# motorboard.net
KiCad netlist of a schematic drawn in EAGLE
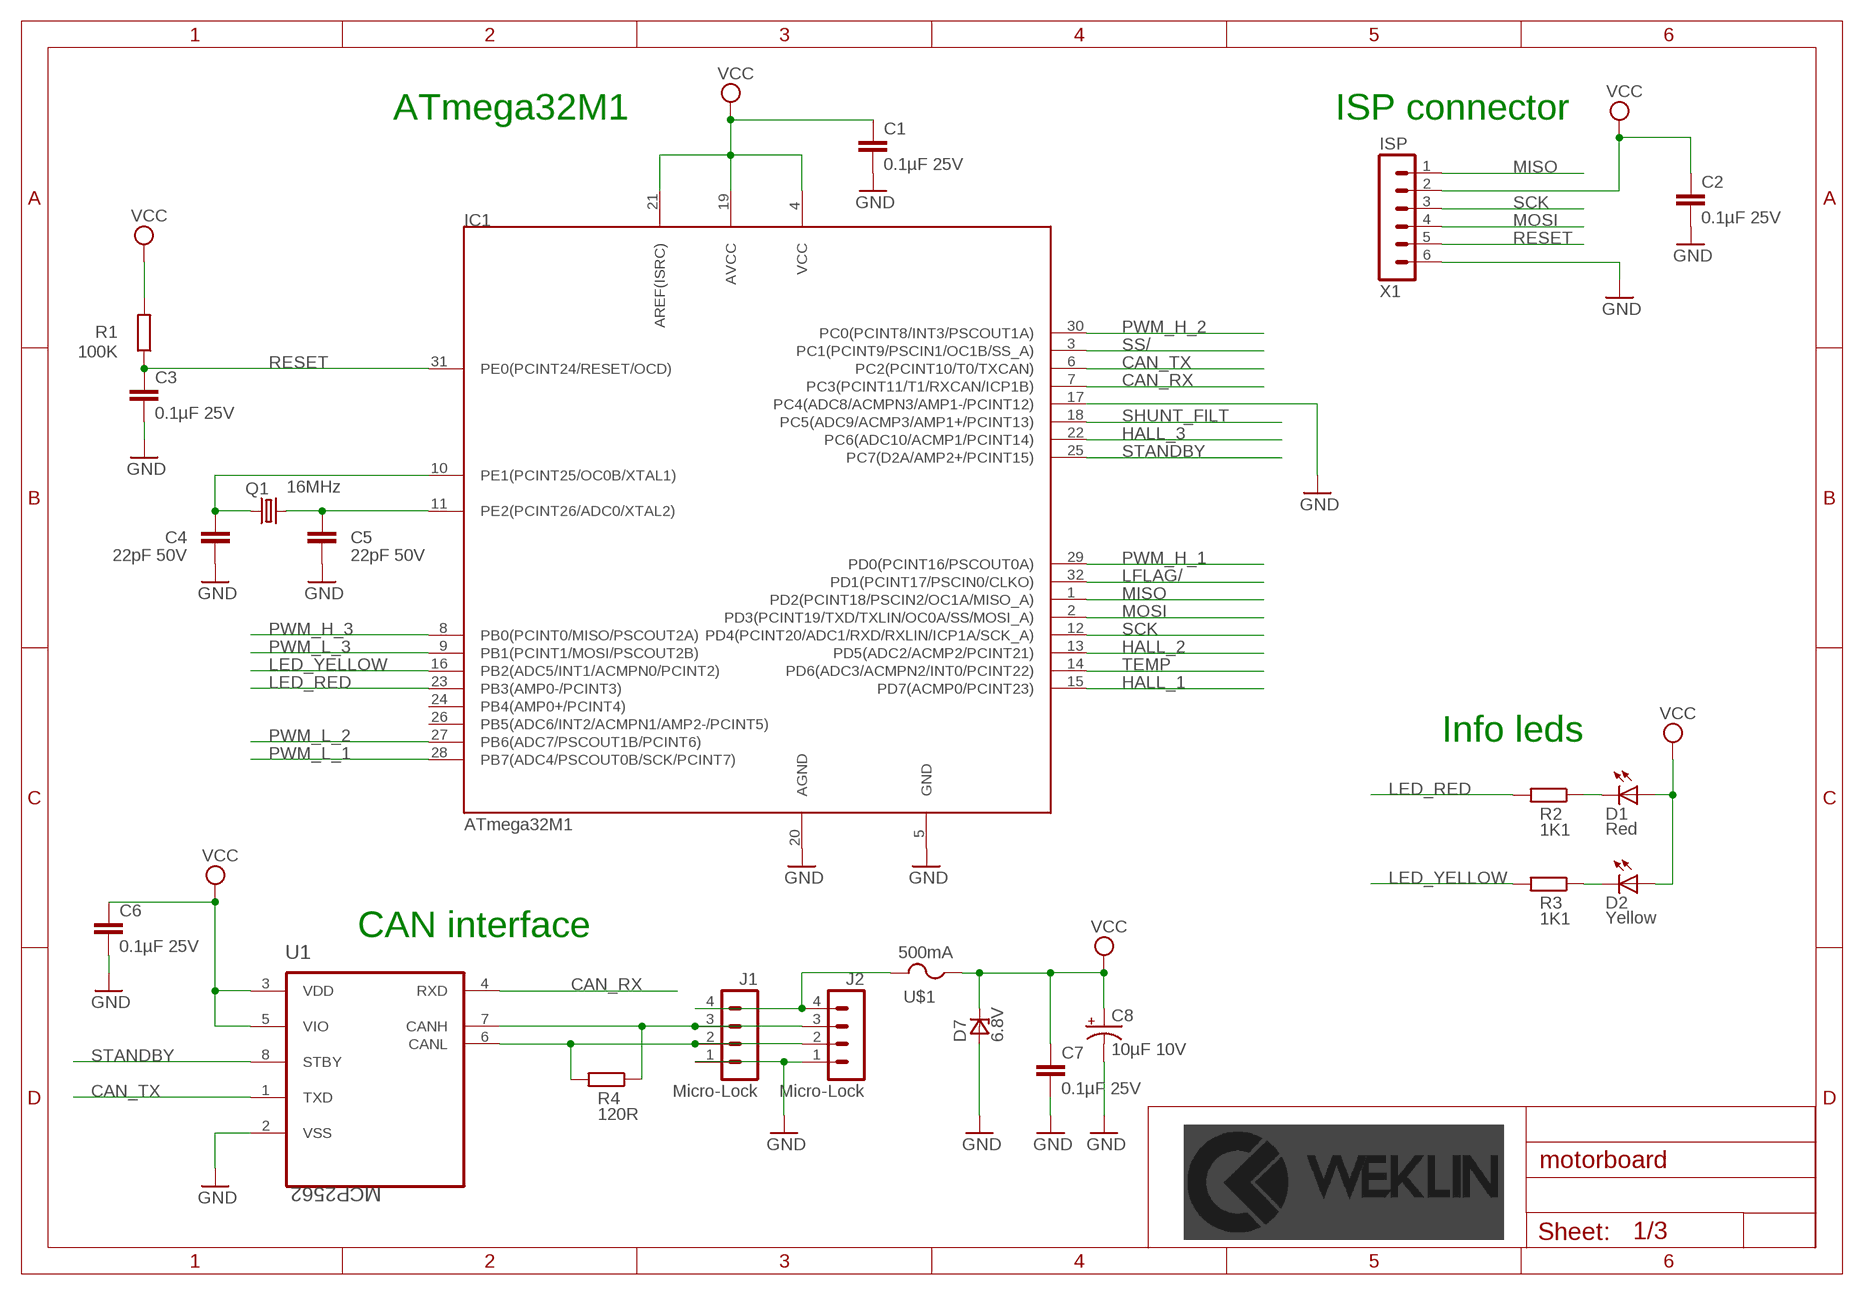
[diagram p0: schematic, sheet 1]
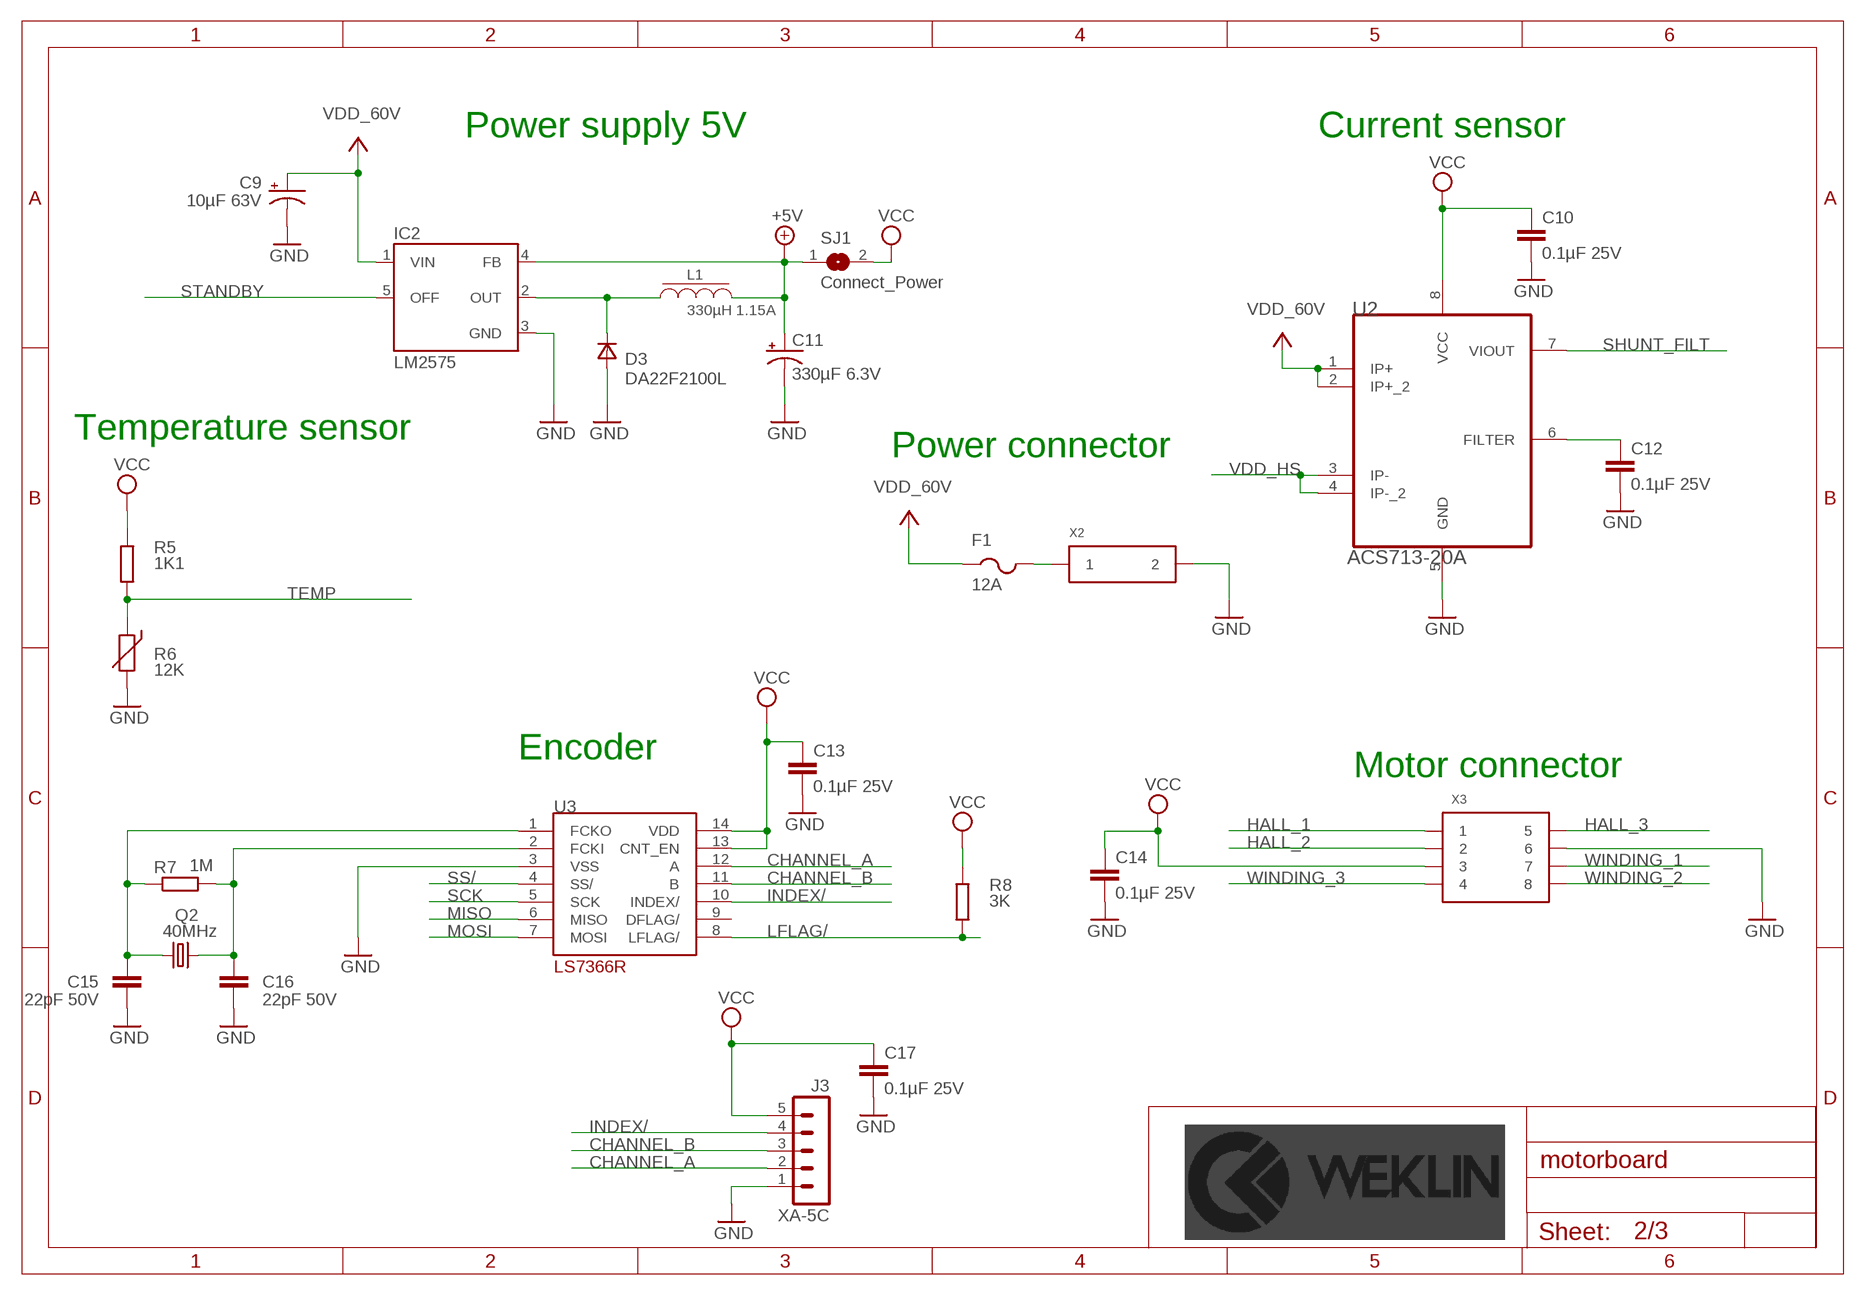
[diagram p1: schematic, sheet 2]
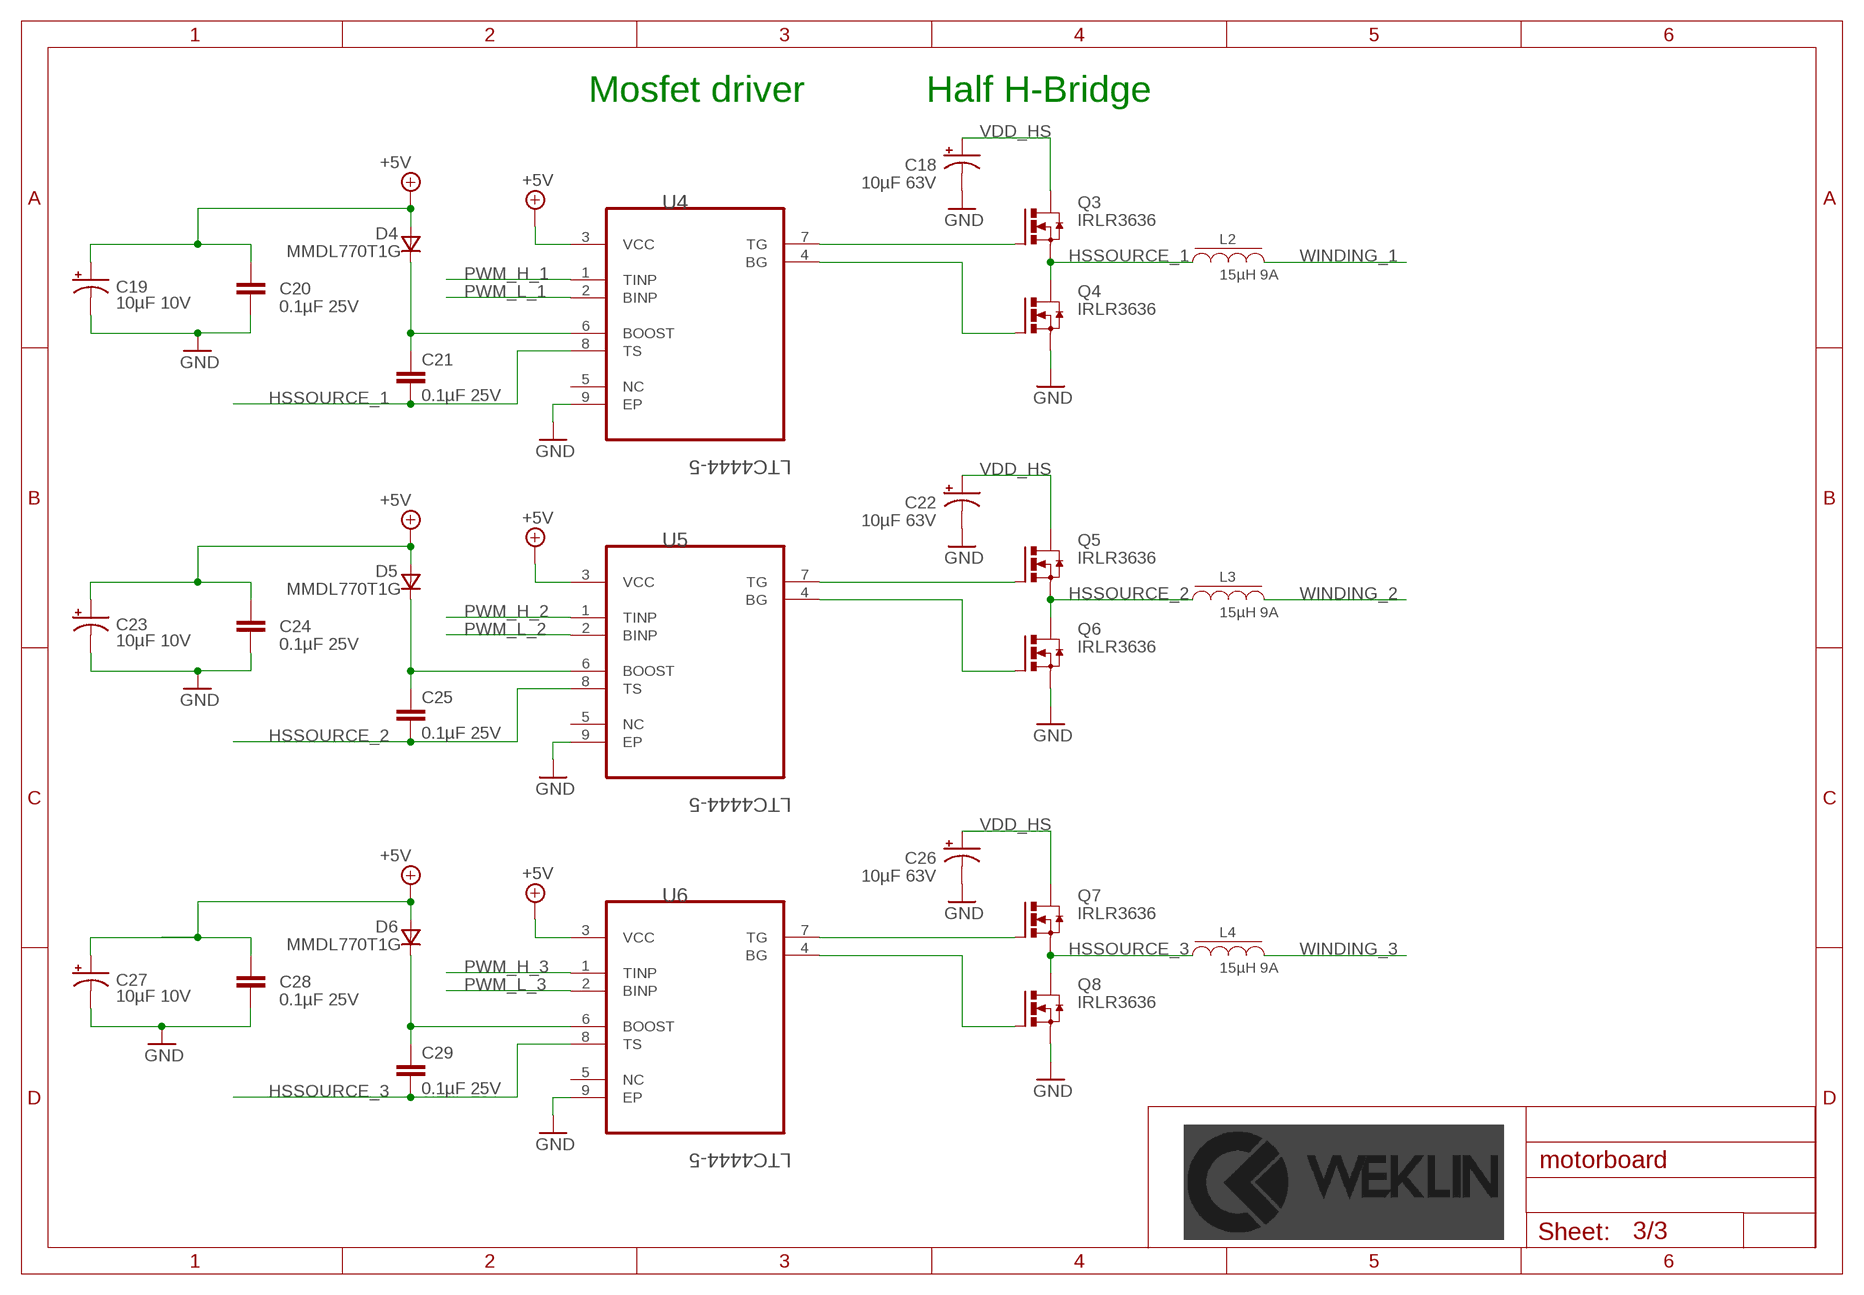
[diagram p2: schematic, sheet 3]

(export (version "E")
  (design (tool "Eeschema 10.0.6"))
  (components
    (comp (ref "C18")
      (value "10µF 63V")
      (footprint "eagle-import:153CLV-1010")
      (fields (field (name "MANUFACTURER") "Nichicon") (field (name "MPN") "UUX1J101MNL1GS"))
      (libsource (lib "eagle-import") (part "CAPACITOR_POL-100µF-63V(+-10%)(1010)"))
    )
    (comp (ref "C19")
      (value "10µF 10V")
      (footprint "eagle-import:EIA3216")
      (fields (field (name "MANUFACTURER") "Kemet") (field (name "MPN") "T491A106K010AT"))
      (libsource (lib "eagle-import") (part "CAPACITOR_POL-10µF-10V(+-10%)(3216)"))
    )
    (comp (ref "C20")
      (value "0.1µF 25V")
      (footprint "eagle-import:C2012")
      (fields (field (name "MANUFACTURER") "AVX") (field (name "MPN") "08053C104KAT2A"))
      (libsource (lib "eagle-import") (part "CAPACITOR_NON_POL-0.1µF-25V(+-10%)(2012)"))
    )
    (comp (ref "C21")
      (value "0.1µF 25V")
      (footprint "eagle-import:C2012")
      (fields (field (name "MANUFACTURER") "AVX") (field (name "MPN") "08053C104KAT2A"))
      (libsource (lib "eagle-import") (part "CAPACITOR_NON_POL-0.1µF-25V(+-10%)(2012)"))
    )
    (comp (ref "C22")
      (value "10µF 63V")
      (footprint "eagle-import:153CLV-1010")
      (fields (field (name "MANUFACTURER") "Nichicon") (field (name "MPN") "UUX1J101MNL1GS"))
      (libsource (lib "eagle-import") (part "CAPACITOR_POL-100µF-63V(+-10%)(1010)"))
    )
    (comp (ref "C23")
      (value "10µF 10V")
      (footprint "eagle-import:EIA3216")
      (fields (field (name "MANUFACTURER") "Kemet") (field (name "MPN") "T491A106K010AT"))
      (libsource (lib "eagle-import") (part "CAPACITOR_POL-10µF-10V(+-10%)(3216)"))
    )
    (comp (ref "C24")
      (value "0.1µF 25V")
      (footprint "eagle-import:C2012")
      (fields (field (name "MANUFACTURER") "AVX") (field (name "MPN") "08053C104KAT2A"))
      (libsource (lib "eagle-import") (part "CAPACITOR_NON_POL-0.1µF-25V(+-10%)(2012)"))
    )
    (comp (ref "C25")
      (value "0.1µF 25V")
      (footprint "eagle-import:C2012")
      (fields (field (name "MANUFACTURER") "AVX") (field (name "MPN") "08053C104KAT2A"))
      (libsource (lib "eagle-import") (part "CAPACITOR_NON_POL-0.1µF-25V(+-10%)(2012)"))
    )
    (comp (ref "C26")
      (value "10µF 63V")
      (footprint "eagle-import:153CLV-1010")
      (fields (field (name "MANUFACTURER") "Nichicon") (field (name "MPN") "UUX1J101MNL1GS"))
      (libsource (lib "eagle-import") (part "CAPACITOR_POL-100µF-63V(+-10%)(1010)"))
    )
    (comp (ref "C27")
      (value "10µF 10V")
      (footprint "eagle-import:EIA3216")
      (fields (field (name "MANUFACTURER") "Kemet") (field (name "MPN") "T491A106K010AT"))
      (libsource (lib "eagle-import") (part "CAPACITOR_POL-10µF-10V(+-10%)(3216)"))
    )
    (comp (ref "C28")
      (value "0.1µF 25V")
      (footprint "eagle-import:C2012")
      (fields (field (name "MANUFACTURER") "AVX") (field (name "MPN") "08053C104KAT2A"))
      (libsource (lib "eagle-import") (part "CAPACITOR_NON_POL-0.1µF-25V(+-10%)(2012)"))
    )
    (comp (ref "C29")
      (value "0.1µF 25V")
      (footprint "eagle-import:C2012")
      (fields (field (name "MANUFACTURER") "AVX") (field (name "MPN") "08053C104KAT2A"))
      (libsource (lib "eagle-import") (part "CAPACITOR_NON_POL-0.1µF-25V(+-10%)(2012)"))
    )
    (comp (ref "D4")
      (value "MMDL770T1G")
      (footprint "eagle-import:SOD323")
      (libsource (lib "eagle-import") (part "DIODE-MMDL770T1G"))
    )
    (comp (ref "D5")
      (value "MMDL770T1G")
      (footprint "eagle-import:SOD323")
      (libsource (lib "eagle-import") (part "DIODE-MMDL770T1G"))
    )
    (comp (ref "D6")
      (value "MMDL770T1G")
      (footprint "eagle-import:SOD323")
      (libsource (lib "eagle-import") (part "DIODE-MMDL770T1G"))
    )
    (comp (ref "L2")
      (value "15µH 9A")
      (footprint "eagle-import:DRA127")
      (fields (field (name "MPN") "SRP1265A-150M"))
      (libsource (lib "eagle-import") (part "SRP1265A-150M"))
    )
    (comp (ref "L3")
      (value "15µH 9A")
      (footprint "eagle-import:DRA127")
      (fields (field (name "MPN") "SRP1265A-150M"))
      (libsource (lib "eagle-import") (part "SRP1265A-150M"))
    )
    (comp (ref "L4")
      (value "15µH 9A")
      (footprint "eagle-import:DRA127")
      (fields (field (name "MPN") "SRP1265A-150M"))
      (libsource (lib "eagle-import") (part "SRP1265A-150M"))
    )
    (comp (ref "Q3")
      (value "IRLR3636")
      (footprint "eagle-import:TO252")
      (fields (field (name "MANUFACTURER") "International Rectifier") (field (name "MPN") "IRLR3636PbF"))
      (libsource (lib "eagle-import") (part "IRLR3636"))
    )
    (comp (ref "Q4")
      (value "IRLR3636")
      (footprint "eagle-import:TO252")
      (fields (field (name "MANUFACTURER") "International Rectifier") (field (name "MPN") "IRLR3636PbF"))
      (libsource (lib "eagle-import") (part "IRLR3636"))
    )
    (comp (ref "Q5")
      (value "IRLR3636")
      (footprint "eagle-import:TO252")
      (fields (field (name "MANUFACTURER") "International Rectifier") (field (name "MPN") "IRLR3636PbF"))
      (libsource (lib "eagle-import") (part "IRLR3636"))
    )
    (comp (ref "Q6")
      (value "IRLR3636")
      (footprint "eagle-import:TO252")
      (fields (field (name "MANUFACTURER") "International Rectifier") (field (name "MPN") "IRLR3636PbF"))
      (libsource (lib "eagle-import") (part "IRLR3636"))
    )
    (comp (ref "Q7")
      (value "IRLR3636")
      (footprint "eagle-import:TO252")
      (fields (field (name "MANUFACTURER") "International Rectifier") (field (name "MPN") "IRLR3636PbF"))
      (libsource (lib "eagle-import") (part "IRLR3636"))
    )
    (comp (ref "Q8")
      (value "IRLR3636")
      (footprint "eagle-import:TO252")
      (fields (field (name "MANUFACTURER") "International Rectifier") (field (name "MPN") "IRLR3636PbF"))
      (libsource (lib "eagle-import") (part "IRLR3636"))
    )
    (comp (ref "U4")
      (value "LTC4444-5")
      (footprint "eagle-import:MSOP8")
      (fields (field (name "MPN") "LTC4444EMS8E-5#PBF"))
      (libsource (lib "eagle-import") (part "LTC4444EMS8EPBF"))
    )
    (comp (ref "U5")
      (value "LTC4444-5")
      (footprint "eagle-import:MSOP8")
      (fields (field (name "MPN") "LTC4444EMS8E-5#PBF"))
      (libsource (lib "eagle-import") (part "LTC4444EMS8EPBF"))
    )
    (comp (ref "U6")
      (value "LTC4444-5")
      (footprint "eagle-import:MSOP8")
      (fields (field (name "MPN") "LTC4444EMS8E-5#PBF"))
      (libsource (lib "eagle-import") (part "LTC4444EMS8EPBF"))
    )
    (comp (ref "C9")
      (value "10µF 63V")
      (footprint "eagle-import:153CLV-1010")
      (fields (field (name "MANUFACTURER") "Nichicon") (field (name "MPN") "UUX1J101MNL1GS"))
      (libsource (lib "eagle-import") (part "CAPACITOR_POL-100µF-63V(+-10%)(1010)"))
    )
    (comp (ref "C10")
      (value "0.1µF 25V")
      (footprint "eagle-import:C2012")
      (fields (field (name "MANUFACTURER") "AVX") (field (name "MPN") "08053C104KAT2A"))
      (libsource (lib "eagle-import") (part "CAPACITOR_NON_POL-0.1µF-25V(+-10%)(2012)"))
    )
    (comp (ref "C11")
      (value "330µF 6.3V")
      (footprint "eagle-import:EIA7343")
      (fields (field (name "MANUFACTURER") "Kemet") (field (name "MPN") "T491D337K006AT"))
      (libsource (lib "eagle-import") (part "CAPACITOR_POL-330µF-6.3V(+-10%)(7343)"))
    )
    (comp (ref "C12")
      (value "0.1µF 25V")
      (footprint "eagle-import:C2012")
      (fields (field (name "MANUFACTURER") "AVX") (field (name "MPN") "08053C104KAT2A"))
      (libsource (lib "eagle-import") (part "CAPACITOR_NON_POL-0.1µF-25V(+-10%)(2012)"))
    )
    (comp (ref "C13")
      (value "0.1µF 25V")
      (footprint "eagle-import:C2012")
      (fields (field (name "MANUFACTURER") "AVX") (field (name "MPN") "08053C104KAT2A"))
      (libsource (lib "eagle-import") (part "CAPACITOR_NON_POL-0.1µF-25V(+-10%)(2012)"))
    )
    (comp (ref "C14")
      (value "0.1µF 25V")
      (footprint "eagle-import:C2012")
      (fields (field (name "MANUFACTURER") "AVX") (field (name "MPN") "08053C104KAT2A"))
      (libsource (lib "eagle-import") (part "CAPACITOR_NON_POL-0.1µF-25V(+-10%)(2012)"))
    )
    (comp (ref "C15")
      (value "22pF 50V")
      (footprint "eagle-import:C2012")
      (fields (field (name "MANUFACTURER") "Multicomp") (field (name "MPN") "MC0805N220J500CT"))
      (libsource (lib "eagle-import") (part "CAPACITOR_NON_POL-22PF-50V(+-5%)(2012)"))
    )
    (comp (ref "C16")
      (value "22pF 50V")
      (footprint "eagle-import:C2012")
      (fields (field (name "MANUFACTURER") "Multicomp") (field (name "MPN") "MC0805N220J500CT"))
      (libsource (lib "eagle-import") (part "CAPACITOR_NON_POL-22PF-50V(+-5%)(2012)"))
    )
    (comp (ref "C17")
      (value "0.1µF 25V")
      (footprint "eagle-import:C2012")
      (fields (field (name "MANUFACTURER") "AVX") (field (name "MPN") "08053C104KAT2A"))
      (libsource (lib "eagle-import") (part "CAPACITOR_NON_POL-0.1µF-25V(+-10%)(2012)"))
    )
    (comp (ref "D3")
      (value "DA22F2100L")
      (footprint "eagle-import:SOD323")
      (libsource (lib "eagle-import") (part "DIODE-DA22F2100L"))
    )
    (comp (ref "F1")
      (value "12A")
      (footprint "eagle-import:R3216")
      (fields (field (name "MPN") "3413.0329.22"))
      (libsource (lib "eagle-import") (part "PTCFUSE-3216(1206)"))
    )
    (comp (ref "IC2")
      (value "LM2575")
      (footprint "eagle-import:TO263-5")
      (fields (field (name "MPN") "LM2575HVS-5.0/NOPB"))
      (libsource (lib "eagle-import") (part "LM2575-TO263"))
    )
    (comp (ref "J3")
      (value "XA-5C")
      (footprint "eagle-import:S05B-XASK-1")
      (fields (field (name "MPN") "S05B-XASK-1(LF)(SN)"))
      (libsource (lib "eagle-import") (part "XA-5-RIGHT_ANGLE"))
    )
    (comp (ref "L1")
      (value "330µH 1.15A")
      (footprint "eagle-import:DRA124")
      (fields (field (name "MPN") "SRR1260A-331K"))
      (libsource (lib "eagle-import") (part "SRR1260A-331K"))
    )
    (comp (ref "Q2")
      (value "40MHz")
      (footprint "eagle-import:SMD_KX7")
      (fields (field (name "MANUFACTURER") "Epson") (field (name "MPN") "X1E0000210488 TSX-3225 "))
      (libsource (lib "eagle-import") (part "CRYSTAL-40MHZ_SMD(3225)"))
    )
    (comp (ref "R5")
      (value "1K1")
      (footprint "eagle-import:R2012")
      (fields (field (name "MANUFACTURER") "Multicomp") (field (name "MPN") "MC0805S8F1101T5E"))
      (libsource (lib "eagle-import") (part "RESISTOR-1K1(+-1%)(2012)"))
    )
    (comp (ref "R6")
      (value "12K")
      (footprint "eagle-import:T2012")
      (fields (field (name "MPN") "NB12L00123KBB"))
      (libsource (lib "eagle-import") (part "NB12L00123KBB-2012(0805)"))
    )
    (comp (ref "R7")
      (value "1M")
      (footprint "eagle-import:R2012")
      (fields (field (name "MPN") "MCWR08X1004FTL"))
      (libsource (lib "eagle-import") (part "RESISTOR-1M(+-1%)(2012)"))
    )
    (comp (ref "R8")
      (value "3K")
      (footprint "eagle-import:R2012")
      (fields (field (name "MPN") "MC0805S8F3001T5E"))
      (libsource (lib "eagle-import") (part "RESISTOR-3K(+-1%)(2012)"))
    )
    (comp (ref "SJ1")
      (value "Connect_Power")
      (footprint "eagle-import:SJ")
      (fields (field (name "MPN") "N.A."))
      (libsource (lib "eagle-import") (part "JUMPER_PCB"))
    )
    (comp (ref "U2")
      (value "ACS713-20A")
      (footprint "eagle-import:SOIC8")
      (fields (field (name "MPN") "ACS713ELCTR-20A-T"))
      (libsource (lib "eagle-import") (part "ASC713713ELCTR-20A-T"))
    )
    (comp (ref "U3")
      (value "LS7366R")
      (footprint "eagle-import:TSSOP14")
      (fields (field (name "MPN") "LS7366R-TS"))
      (libsource (lib "eagle-import") (part "LS7366R-TS-TSSOP14"))
    )
    (comp (ref "X2")
      (value "Mini-Fit")
      (footprint "eagle-import:5569-02")
      (fields (field (name "MANUFACTURER") "Molex") (field (name "MPN") "39-29-1028"))
      (libsource (lib "eagle-import") (part "MINI-FIT-JR-025569-NA1"))
    )
    (comp (ref "X3")
      (value "Mini-Fit")
      (footprint "eagle-import:5569-08")
      (fields (field (name "MANUFACTURER") "MOLEX") (field (name "MPN") "39-29-1088"))
      (libsource (lib "eagle-import") (part "MINI-FIT-JR-085569-NA1"))
    )
    (comp (ref "C1")
      (value "0.1µF 25V")
      (footprint "eagle-import:C2012")
      (fields (field (name "MANUFACTURER") "AVX") (field (name "MPN") "08053C104KAT2A"))
      (libsource (lib "eagle-import") (part "CAPACITOR_NON_POL-0.1µF-25V(+-10%)(2012)"))
    )
    (comp (ref "C2")
      (value "0.1µF 25V")
      (footprint "eagle-import:C2012")
      (fields (field (name "MANUFACTURER") "AVX") (field (name "MPN") "08053C104KAT2A"))
      (libsource (lib "eagle-import") (part "CAPACITOR_NON_POL-0.1µF-25V(+-10%)(2012)"))
    )
    (comp (ref "C3")
      (value "0.1µF 25V")
      (footprint "eagle-import:C2012")
      (fields (field (name "MANUFACTURER") "AVX") (field (name "MPN") "08053C104KAT2A"))
      (libsource (lib "eagle-import") (part "CAPACITOR_NON_POL-0.1µF-25V(+-10%)(2012)"))
    )
    (comp (ref "C4")
      (value "22pF 50V")
      (footprint "eagle-import:C2012")
      (fields (field (name "MANUFACTURER") "Multicomp") (field (name "MPN") "MC0805N220J500CT"))
      (libsource (lib "eagle-import") (part "CAPACITOR_NON_POL-22PF-50V(+-5%)(2012)"))
    )
    (comp (ref "C5")
      (value "22pF 50V")
      (footprint "eagle-import:C2012")
      (fields (field (name "MANUFACTURER") "Multicomp") (field (name "MPN") "MC0805N220J500CT"))
      (libsource (lib "eagle-import") (part "CAPACITOR_NON_POL-22PF-50V(+-5%)(2012)"))
    )
    (comp (ref "C6")
      (value "0.1µF 25V")
      (footprint "eagle-import:C2012")
      (fields (field (name "MANUFACTURER") "AVX") (field (name "MPN") "08053C104KAT2A"))
      (libsource (lib "eagle-import") (part "CAPACITOR_NON_POL-0.1µF-25V(+-10%)(2012)"))
    )
    (comp (ref "C7")
      (value "0.1µF 25V")
      (footprint "eagle-import:C2012")
      (fields (field (name "MANUFACTURER") "AVX") (field (name "MPN") "08053C104KAT2A"))
      (libsource (lib "eagle-import") (part "CAPACITOR_NON_POL-0.1µF-25V(+-10%)(2012)"))
    )
    (comp (ref "C8")
      (value "10µF 10V")
      (footprint "eagle-import:EIA3216")
      (fields (field (name "MANUFACTURER") "Kemet") (field (name "MPN") "T491A106K010AT"))
      (libsource (lib "eagle-import") (part "CAPACITOR_POL-10µF-10V(+-10%)(3216)"))
    )
    (comp (ref "D1")
      (value "Red")
      (footprint "eagle-import:VLD")
      (fields (field (name "MANUFACTURER") "Vishay") (field (name "MPN") "VLDS1235G"))
      (libsource (lib "eagle-import") (part "LEDVLDS1235G"))
    )
    (comp (ref "D2")
      (value "Yellow")
      (footprint "eagle-import:VLD")
      (fields (field (name "MANUFACTURER") "Vishay") (field (name "MPN") "VLDY1235G"))
      (libsource (lib "eagle-import") (part "LED-VLDY1235G"))
    )
    (comp (ref "D7")
      (value "6.8V")
      (footprint "eagle-import:DO-214AA")
      (fields (field (name "MANUFACTURER") "ON Semiconductor") (field (name "MPN") "P6SMB6.8AT3G"))
      (libsource (lib "eagle-import") (part "ZENER_UNIDIR6.8"))
    )
    (comp (ref "IC1")
      (value "ATmega32M1")
      (footprint "eagle-import:TQFP32")
      (fields (field (name "MANUFACTURER") "Atmel") (field (name "MPN") "ATmega32M1-AU"))
      (libsource (lib "eagle-import") (part "ATMEGA32M1-TQFP32"))
    )
    (comp (ref "J1")
      (value "Micro-Lock")
      (footprint "eagle-import:504195-0470")
      (fields (field (name "MANUFACTURER") "Molex") (field (name "MPN") "504195-0470"))
      (libsource (lib "eagle-import") (part "MICROLOCK-4CMS"))
    )
    (comp (ref "J2")
      (value "Micro-Lock")
      (footprint "eagle-import:504195-0470")
      (fields (field (name "MANUFACTURER") "Molex") (field (name "MPN") "504195-0470"))
      (libsource (lib "eagle-import") (part "MICROLOCK-4CMS"))
    )
    (comp (ref "Q1")
      (value "16MHz")
      (footprint "eagle-import:SMD_KX7")
      (fields (field (name "MANUFACTURER") "AEL CRYSTALS") (field (name "MPN") "E3SB16.0000F09G11AE"))
      (libsource (lib "eagle-import") (part "CRYSTAL-16MHZ_SMD(3225)"))
    )
    (comp (ref "R1")
      (value "100K")
      (footprint "eagle-import:R2012")
      (fields (field (name "MANUFACTURER") "Multicomp") (field (name "MPN") "MCWR08X1003FTL"))
      (libsource (lib "eagle-import") (part "RESISTOR-100K(+-1%)(2012)"))
    )
    (comp (ref "R2")
      (value "1K1")
      (footprint "eagle-import:R2012")
      (fields (field (name "MANUFACTURER") "Multicomp") (field (name "MPN") "MC0805S8F1101T5E"))
      (libsource (lib "eagle-import") (part "RESISTOR-1K1(+-1%)(2012)"))
    )
    (comp (ref "R3")
      (value "1K1")
      (footprint "eagle-import:R2012")
      (fields (field (name "MANUFACTURER") "Multicomp") (field (name "MPN") "MC0805S8F1101T5E"))
      (libsource (lib "eagle-import") (part "RESISTOR-1K1(+-1%)(2012)"))
    )
    (comp (ref "R4")
      (value "120R")
      (footprint "eagle-import:R2012")
      (fields (field (name "MANUFACTURER") "Multicomp") (field (name "MPN") "MCWR08X1200FTL"))
      (libsource (lib "eagle-import") (part "RESISTOR-120R(+-1%)(2012)"))
    )
    (comp (ref "U$1")
      (value "500mA")
      (footprint "eagle-import:EIARS-481-2")
      (fields (field (name "MANUFACTURER") "Littlefuse") (field (name "MPN") "0451.500MRL"))
      (libsource (lib "eagle-import") (part "FUSE"))
    )
    (comp (ref "U1")
      (value "MCP2562")
      (footprint "eagle-import:SOIC8")
      (fields (field (name "MANUFACTURER") "Microchip") (field (name "MPN") "MCP2562-E/SN"))
      (libsource (lib "eagle-import") (part "MCP2562-E/SN-SOIC8"))
    )
    (comp (ref "X1")
      (value "ISP")
      (footprint "eagle-import:MINITEK_127_6WAY_SMD")
      (fields (field (name "MANUFACTURER") "Minitek") (field (name "MPN") "20021121-00006C4LF"))
      (libsource (lib "eagle-import") (part "MINITEK_127_6WAYS-SMD"))
    )
  )
  (nets
    (net (code "1") (name "+5V") (class "Default")
      (node (ref "C11") (pin "A") (pinfunction "+_A") (pintype "passive"))
      (node (ref "C19") (pin "A") (pinfunction "+_A") (pintype "passive"))
      (node (ref "C20") (pin "1") (pinfunction "1_1") (pintype "passive"))
      (node (ref "C23") (pin "A") (pinfunction "+_A") (pintype "passive"))
      (node (ref "C24") (pin "1") (pinfunction "1_1") (pintype "passive"))
      (node (ref "C27") (pin "A") (pinfunction "+_A") (pintype "passive"))
      (node (ref "C28") (pin "1") (pinfunction "1_1") (pintype "passive"))
      (node (ref "D4") (pin "2") (pinfunction "A_2") (pintype "passive"))
      (node (ref "D5") (pin "2") (pinfunction "A_2") (pintype "passive"))
      (node (ref "D6") (pin "2") (pinfunction "A_2") (pintype "passive"))
      (node (ref "IC2") (pin "4") (pinfunction "FB_4") (pintype "input"))
      (node (ref "L1") (pin "2") (pinfunction "2_2") (pintype "passive"))
      (node (ref "SJ1") (pin "1") (pinfunction "1_1") (pintype "passive"))
      (node (ref "U4") (pin "3") (pinfunction "VCC_3") (pintype "power_in"))
      (node (ref "U5") (pin "3") (pinfunction "VCC_3") (pintype "power_in"))
      (node (ref "U6") (pin "3") (pinfunction "VCC_3") (pintype "power_in"))
    )
    (net (code "2") (name "CAN_RX") (class "Default")
      (node (ref "IC1") (pin "7") (pinfunction "PC3(PCINT11/T1/RXCAN/ICP1B)_7") (pintype "bidirectional"))
      (node (ref "U1") (pin "4") (pinfunction "RXD_4") (pintype "output"))
    )
    (net (code "3") (name "CAN_TX") (class "Default")
      (node (ref "IC1") (pin "6") (pinfunction "PC2(PCINT10/T0/TXCAN)_6") (pintype "bidirectional"))
      (node (ref "U1") (pin "1") (pinfunction "TXD_1") (pintype "input"))
    )
    (net (code "4") (name "CHANNEL_A") (class "Default")
      (node (ref "J3") (pin "2") (pinfunction "2_2") (pintype "passive"))
      (node (ref "U3") (pin "12") (pinfunction "A_12") (pintype "bidirectional"))
    )
    (net (code "5") (name "CHANNEL_B") (class "Default")
      (node (ref "J3") (pin "3") (pinfunction "3_3") (pintype "passive"))
      (node (ref "U3") (pin "11") (pinfunction "B_11") (pintype "bidirectional"))
    )
    (net (code "6") (name "GND") (class "Default")
      (node (ref "C1") (pin "2") (pinfunction "2_2") (pintype "passive"))
      (node (ref "C10") (pin "2") (pinfunction "2_2") (pintype "passive"))
      (node (ref "C11") (pin "C") (pinfunction "-_C") (pintype "passive"))
      (node (ref "C12") (pin "2") (pinfunction "2_2") (pintype "passive"))
      (node (ref "C13") (pin "2") (pinfunction "2_2") (pintype "passive"))
      (node (ref "C14") (pin "2") (pinfunction "2_2") (pintype "passive"))
      (node (ref "C15") (pin "2") (pinfunction "2_2") (pintype "passive"))
      (node (ref "C16") (pin "2") (pinfunction "2_2") (pintype "passive"))
      (node (ref "C17") (pin "2") (pinfunction "2_2") (pintype "passive"))
      (node (ref "C18") (pin "-") (pinfunction "-_-") (pintype "passive"))
      (node (ref "C19") (pin "C") (pinfunction "-_C") (pintype "passive"))
      (node (ref "C2") (pin "2") (pinfunction "2_2") (pintype "passive"))
      (node (ref "C20") (pin "2") (pinfunction "2_2") (pintype "passive"))
      (node (ref "C22") (pin "-") (pinfunction "-_-") (pintype "passive"))
      (node (ref "C23") (pin "C") (pinfunction "-_C") (pintype "passive"))
      (node (ref "C24") (pin "2") (pinfunction "2_2") (pintype "passive"))
      (node (ref "C26") (pin "-") (pinfunction "-_-") (pintype "passive"))
      (node (ref "C27") (pin "C") (pinfunction "-_C") (pintype "passive"))
      (node (ref "C28") (pin "2") (pinfunction "2_2") (pintype "passive"))
      (node (ref "C3") (pin "2") (pinfunction "2_2") (pintype "passive"))
      (node (ref "C4") (pin "2") (pinfunction "2_2") (pintype "passive"))
      (node (ref "C5") (pin "2") (pinfunction "2_2") (pintype "passive"))
      (node (ref "C6") (pin "2") (pinfunction "2_2") (pintype "passive"))
      (node (ref "C7") (pin "2") (pinfunction "2_2") (pintype "passive"))
      (node (ref "C8") (pin "C") (pinfunction "-_C") (pintype "passive"))
      (node (ref "C9") (pin "-") (pinfunction "-_-") (pintype "passive"))
      (node (ref "D3") (pin "2") (pinfunction "A_2") (pintype "passive"))
      (node (ref "D7") (pin "A") (pinfunction "A_A") (pintype "passive"))
      (node (ref "IC1") (pin "17") (pinfunction "PC4(ADC8/ACMPN3/AMP1-/PCINT12)_17") (pintype "bidirectional"))
      (node (ref "IC1") (pin "20") (pinfunction "AGND_20") (pintype "power_in"))
      (node (ref "IC1") (pin "5") (pinfunction "GND_5") (pintype "power_in"))
      (node (ref "IC2") (pin "3") (pinfunction "GND_3") (pintype "power_in"))
      (node (ref "J1") (pin "1") (pinfunction "1_1") (pintype "passive"))
      (node (ref "J2") (pin "1") (pinfunction "1_1") (pintype "passive"))
      (node (ref "J3") (pin "1") (pinfunction "1_1") (pintype "passive"))
      (node (ref "Q4") (pin "3") (pinfunction "S_3") (pintype "passive"))
      (node (ref "Q6") (pin "3") (pinfunction "S_3") (pintype "passive"))
      (node (ref "Q8") (pin "3") (pinfunction "S_3") (pintype "passive"))
      (node (ref "R6") (pin "2") (pinfunction "2_2") (pintype "passive"))
      (node (ref "U1") (pin "2") (pinfunction "VSS_2") (pintype "power_in"))
      (node (ref "U2") (pin "5") (pinfunction "GND_5") (pintype "passive"))
      (node (ref "U3") (pin "3") (pinfunction "VSS_3") (pintype "bidirectional"))
      (node (ref "U4") (pin "9") (pinfunction "EP_9") (pintype "passive"))
      (node (ref "U5") (pin "9") (pinfunction "EP_9") (pintype "passive"))
      (node (ref "U6") (pin "9") (pinfunction "EP_9") (pintype "passive"))
      (node (ref "X1") (pin "6") (pinfunction "6_6") (pintype "passive"))
      (node (ref "X2") (pin "P2") (pinfunction "2_P2") (pintype "bidirectional"))
      (node (ref "X3") (pin "P6") (pinfunction "6_P6") (pintype "bidirectional"))
    )
    (net (code "7") (name "HALL_1") (class "Default")
      (node (ref "IC1") (pin "15") (pinfunction "PD7(ACMP0/PCINT23)_15") (pintype "bidirectional"))
      (node (ref "X3") (pin "P1") (pinfunction "1_P1") (pintype "bidirectional"))
    )
    (net (code "8") (name "HALL_2") (class "Default")
      (node (ref "IC1") (pin "13") (pinfunction "PD5(ADC2/ACMP2/PCINT21)_13") (pintype "bidirectional"))
      (node (ref "X3") (pin "P2") (pinfunction "2_P2") (pintype "bidirectional"))
    )
    (net (code "9") (name "HALL_3") (class "Default")
      (node (ref "IC1") (pin "22") (pinfunction "PC6(ADC10/ACMP1/PCINT14)_22") (pintype "bidirectional"))
      (node (ref "X3") (pin "P5") (pinfunction "5_P5") (pintype "bidirectional"))
    )
    (net (code "10") (name "HSSOURCE_1") (class "Default")
      (node (ref "C21") (pin "2") (pinfunction "2_2") (pintype "passive"))
      (node (ref "L2") (pin "1") (pinfunction "1_1") (pintype "passive"))
      (node (ref "Q3") (pin "3") (pinfunction "S_3") (pintype "passive"))
      (node (ref "Q4") (pin "4") (pinfunction "D_4") (pintype "passive"))
      (node (ref "U4") (pin "8") (pinfunction "TS_8") (pintype "input"))
    )
    (net (code "11") (name "HSSOURCE_2") (class "Default")
      (node (ref "C25") (pin "2") (pinfunction "2_2") (pintype "passive"))
      (node (ref "L3") (pin "1") (pinfunction "1_1") (pintype "passive"))
      (node (ref "Q5") (pin "3") (pinfunction "S_3") (pintype "passive"))
      (node (ref "Q6") (pin "4") (pinfunction "D_4") (pintype "passive"))
      (node (ref "U5") (pin "8") (pinfunction "TS_8") (pintype "input"))
    )
    (net (code "12") (name "HSSOURCE_3") (class "Default")
      (node (ref "C29") (pin "2") (pinfunction "2_2") (pintype "passive"))
      (node (ref "L4") (pin "1") (pinfunction "1_1") (pintype "passive"))
      (node (ref "Q7") (pin "3") (pinfunction "S_3") (pintype "passive"))
      (node (ref "Q8") (pin "4") (pinfunction "D_4") (pintype "passive"))
      (node (ref "U6") (pin "8") (pinfunction "TS_8") (pintype "input"))
    )
    (net (code "13") (name "INDEX{slash}") (class "Default")
      (node (ref "J3") (pin "4") (pinfunction "4_4") (pintype "passive"))
      (node (ref "U3") (pin "10") (pinfunction "INDEX/_10") (pintype "bidirectional"))
    )
    (net (code "14") (name "LED_RED") (class "Default")
      (node (ref "IC1") (pin "23") (pinfunction "PB3(AMP0-/PCINT3)_23") (pintype "bidirectional"))
      (node (ref "R2") (pin "2") (pinfunction "2_2") (pintype "passive"))
    )
    (net (code "15") (name "LED_YELLOW") (class "Default")
      (node (ref "IC1") (pin "16") (pinfunction "PB2(ADC5/INT1/ACMPN0/PCINT2)_16") (pintype "bidirectional"))
      (node (ref "R3") (pin "2") (pinfunction "2_2") (pintype "passive"))
    )
    (net (code "16") (name "LFLAG{slash}") (class "Default")
      (node (ref "IC1") (pin "32") (pinfunction "PD1(PCINT17/PSCIN0/CLKO)_32") (pintype "bidirectional"))
      (node (ref "R8") (pin "2") (pinfunction "2_2") (pintype "passive"))
      (node (ref "U3") (pin "8") (pinfunction "LFLAG/_8") (pintype "bidirectional"))
    )
    (net (code "17") (name "MISO") (class "Default")
      (node (ref "IC1") (pin "1") (pinfunction "PD2(PCINT18/PSCIN2/OC1A/MISO_A)_1") (pintype "bidirectional"))
      (node (ref "U3") (pin "6") (pinfunction "MISO_6") (pintype "bidirectional"))
      (node (ref "X1") (pin "1") (pinfunction "1_1") (pintype "passive"))
    )
    (net (code "18") (name "MOSI") (class "Default")
      (node (ref "IC1") (pin "2") (pinfunction "PD3(PCINT19/TXD/TXLIN/OC0A/SS/MOSI_A)_2") (pintype "bidirectional"))
      (node (ref "U3") (pin "7") (pinfunction "MOSI_7") (pintype "bidirectional"))
      (node (ref "X1") (pin "4") (pinfunction "4_4") (pintype "passive"))
    )
    (net (code "19") (name "Net-(D1-PadC)") (class "Default")
      (node (ref "D1") (pin "C") (pinfunction "C_C") (pintype "passive"))
      (node (ref "R2") (pin "1") (pinfunction "1_1") (pintype "passive"))
    )
    (net (code "20") (name "Net-(D2-PadC)") (class "Default")
      (node (ref "D2") (pin "C") (pinfunction "C_C") (pintype "passive"))
      (node (ref "R3") (pin "1") (pinfunction "1_1") (pintype "passive"))
    )
    (net (code "21") (name "Net-(D3-C)") (class "Default")
      (node (ref "D3") (pin "1") (pinfunction "C_1") (pintype "passive"))
      (node (ref "IC2") (pin "2") (pinfunction "OUT_2") (pintype "output"))
      (node (ref "L1") (pin "1") (pinfunction "1_1") (pintype "passive"))
    )
    (net (code "22") (name "Net-(D4-C)") (class "Default")
      (node (ref "C21") (pin "1") (pinfunction "1_1") (pintype "passive"))
      (node (ref "D4") (pin "1") (pinfunction "C_1") (pintype "passive"))
      (node (ref "U4") (pin "6") (pinfunction "BOOST_6") (pintype "power_in"))
    )
    (net (code "23") (name "Net-(D5-C)") (class "Default")
      (node (ref "C25") (pin "1") (pinfunction "1_1") (pintype "passive"))
      (node (ref "D5") (pin "1") (pinfunction "C_1") (pintype "passive"))
      (node (ref "U5") (pin "6") (pinfunction "BOOST_6") (pintype "power_in"))
    )
    (net (code "24") (name "Net-(D6-C)") (class "Default")
      (node (ref "C29") (pin "1") (pinfunction "1_1") (pintype "passive"))
      (node (ref "D6") (pin "1") (pinfunction "C_1") (pintype "passive"))
      (node (ref "U6") (pin "6") (pinfunction "BOOST_6") (pintype "power_in"))
    )
    (net (code "25") (name "Net-(IC1-PE1(PCINT25{slash}OC0B{slash}XTAL1))") (class "Default")
      (node (ref "C4") (pin "1") (pinfunction "1_1") (pintype "passive"))
      (node (ref "IC1") (pin "10") (pinfunction "PE1(PCINT25/OC0B/XTAL1)_10") (pintype "bidirectional"))
      (node (ref "Q1") (pin "1") (pinfunction "1_1") (pintype "passive"))
    )
    (net (code "26") (name "Net-(IC1-PE2(PCINT26{slash}ADC0{slash}XTAL2))") (class "Default")
      (node (ref "C5") (pin "1") (pinfunction "1_1") (pintype "passive"))
      (node (ref "IC1") (pin "11") (pinfunction "PE2(PCINT26/ADC0/XTAL2)_11") (pintype "bidirectional"))
      (node (ref "Q1") (pin "3") (pinfunction "2_3") (pintype "passive"))
    )
    (net (code "27") (name "Net-(J1-Pad4)") (class "Default")
      (node (ref "J1") (pin "4") (pinfunction "4_4") (pintype "passive"))
      (node (ref "J2") (pin "4") (pinfunction "4_4") (pintype "passive"))
      (node (ref "U$1") (pin "2") (pinfunction "2_2") (pintype "passive"))
    )
    (net (code "28") (name "Net-(Q2-2)") (class "Default")
      (node (ref "C16") (pin "1") (pinfunction "1_1") (pintype "passive"))
      (node (ref "Q2") (pin "3") (pinfunction "2_3") (pintype "passive"))
      (node (ref "R7") (pin "2") (pinfunction "2_2") (pintype "passive"))
      (node (ref "U3") (pin "2") (pinfunction "FCKI_2") (pintype "bidirectional"))
    )
    (net (code "29") (name "Net-(Q3-G)") (class "Default")
      (node (ref "Q3") (pin "1") (pinfunction "G_1") (pintype "passive"))
      (node (ref "U4") (pin "7") (pinfunction "TG_7") (pintype "output"))
    )
    (net (code "30") (name "Net-(Q4-G)") (class "Default")
      (node (ref "Q4") (pin "1") (pinfunction "G_1") (pintype "passive"))
      (node (ref "U4") (pin "4") (pinfunction "BG_4") (pintype "output"))
    )
    (net (code "31") (name "Net-(Q5-G)") (class "Default")
      (node (ref "Q5") (pin "1") (pinfunction "G_1") (pintype "passive"))
      (node (ref "U5") (pin "7") (pinfunction "TG_7") (pintype "output"))
    )
    (net (code "32") (name "Net-(Q6-G)") (class "Default")
      (node (ref "Q6") (pin "1") (pinfunction "G_1") (pintype "passive"))
      (node (ref "U5") (pin "4") (pinfunction "BG_4") (pintype "output"))
    )
    (net (code "33") (name "Net-(Q7-G)") (class "Default")
      (node (ref "Q7") (pin "1") (pinfunction "G_1") (pintype "passive"))
      (node (ref "U6") (pin "7") (pinfunction "TG_7") (pintype "output"))
    )
    (net (code "34") (name "Net-(Q8-G)") (class "Default")
      (node (ref "Q8") (pin "1") (pinfunction "G_1") (pintype "passive"))
      (node (ref "U6") (pin "4") (pinfunction "BG_4") (pintype "output"))
    )
    (net (code "35") (name "Net-(U1-CANH)") (class "Default")
      (node (ref "J1") (pin "3") (pinfunction "3_3") (pintype "passive"))
      (node (ref "J2") (pin "3") (pinfunction "3_3") (pintype "passive"))
      (node (ref "R4") (pin "1") (pinfunction "1_1") (pintype "passive"))
      (node (ref "U1") (pin "7") (pinfunction "CANH_7") (pintype "bidirectional"))
    )
    (net (code "36") (name "Net-(U1-CANL)") (class "Default")
      (node (ref "J1") (pin "2") (pinfunction "2_2") (pintype "passive"))
      (node (ref "J2") (pin "2") (pinfunction "2_2") (pintype "passive"))
      (node (ref "R4") (pin "2") (pinfunction "2_2") (pintype "passive"))
      (node (ref "U1") (pin "6") (pinfunction "CANL_6") (pintype "bidirectional"))
    )
    (net (code "37") (name "Net-(U2-FILTER)") (class "Default")
      (node (ref "C12") (pin "1") (pinfunction "1_1") (pintype "passive"))
      (node (ref "U2") (pin "6") (pinfunction "FILTER_6") (pintype "input"))
    )
    (net (code "38") (name "Net-(U3-FCKO)") (class "Default")
      (node (ref "C15") (pin "1") (pinfunction "1_1") (pintype "passive"))
      (node (ref "Q2") (pin "1") (pinfunction "1_1") (pintype "passive"))
      (node (ref "R7") (pin "1") (pinfunction "1_1") (pintype "passive"))
      (node (ref "U3") (pin "1") (pinfunction "FCKO_1") (pintype "bidirectional"))
    )
    (net (code "39") (name "Net-(X2-1)") (class "Default")
      (node (ref "F1") (pin "2") (pinfunction "2_2") (pintype "passive"))
      (node (ref "X2") (pin "P1") (pinfunction "1_P1") (pintype "bidirectional"))
    )
    (net (code "40") (name "PWM_H_1") (class "Default")
      (node (ref "IC1") (pin "29") (pinfunction "PD0(PCINT16/PSCOUT0A)_29") (pintype "bidirectional"))
      (node (ref "U4") (pin "1") (pinfunction "TINP_1") (pintype "input"))
    )
    (net (code "41") (name "PWM_H_2") (class "Default")
      (node (ref "IC1") (pin "30") (pinfunction "PC0(PCINT8/INT3/PSCOUT1A)_30") (pintype "bidirectional"))
      (node (ref "U5") (pin "1") (pinfunction "TINP_1") (pintype "input"))
    )
    (net (code "42") (name "PWM_H_3") (class "Default")
      (node (ref "IC1") (pin "8") (pinfunction "PB0(PCINT0/MISO/PSCOUT2A)_8") (pintype "bidirectional"))
      (node (ref "U6") (pin "1") (pinfunction "TINP_1") (pintype "input"))
    )
    (net (code "43") (name "PWM_L_1") (class "Default")
      (node (ref "IC1") (pin "28") (pinfunction "PB7(ADC4/PSCOUT0B/SCK/PCINT7)_28") (pintype "bidirectional"))
      (node (ref "U4") (pin "2") (pinfunction "BINP_2") (pintype "input"))
    )
    (net (code "44") (name "PWM_L_2") (class "Default")
      (node (ref "IC1") (pin "27") (pinfunction "PB6(ADC7/PSCOUT1B/PCINT6)_27") (pintype "bidirectional"))
      (node (ref "U5") (pin "2") (pinfunction "BINP_2") (pintype "input"))
    )
    (net (code "45") (name "PWM_L_3") (class "Default")
      (node (ref "IC1") (pin "9") (pinfunction "PB1(PCINT1/MOSI/PSCOUT2B)_9") (pintype "bidirectional"))
      (node (ref "U6") (pin "2") (pinfunction "BINP_2") (pintype "input"))
    )
    (net (code "46") (name "RESET") (class "Default")
      (node (ref "C3") (pin "1") (pinfunction "1_1") (pintype "passive"))
      (node (ref "IC1") (pin "31") (pinfunction "PE0(PCINT24/RESET/OCD)_31") (pintype "bidirectional"))
      (node (ref "R1") (pin "1") (pinfunction "1_1") (pintype "passive"))
      (node (ref "X1") (pin "5") (pinfunction "5_5") (pintype "passive"))
    )
    (net (code "47") (name "SCK") (class "Default")
      (node (ref "IC1") (pin "12") (pinfunction "PD4(PCINT20/ADC1/RXD/RXLIN/ICP1A/SCK_A)_12") (pintype "bidirectional"))
      (node (ref "U3") (pin "5") (pinfunction "SCK_5") (pintype "bidirectional"))
      (node (ref "X1") (pin "3") (pinfunction "3_3") (pintype "passive"))
    )
    (net (code "48") (name "SHUNT_FILT") (class "Default")
      (node (ref "IC1") (pin "18") (pinfunction "PC5(ADC9/ACMP3/AMP1+/PCINT13)_18") (pintype "bidirectional"))
      (node (ref "U2") (pin "7") (pinfunction "VIOUT_7") (pintype "output"))
    )
    (net (code "49") (name "SS{slash}") (class "Default")
      (node (ref "IC1") (pin "3") (pinfunction "PC1(PCINT9/PSCIN1/OC1B/SS_A)_3") (pintype "bidirectional"))
      (node (ref "U3") (pin "4") (pinfunction "SS/_4") (pintype "bidirectional"))
    )
    (net (code "50") (name "STANDBY") (class "Default")
      (node (ref "IC1") (pin "25") (pinfunction "PC7(D2A/AMP2+/PCINT15)_25") (pintype "bidirectional"))
      (node (ref "IC2") (pin "5") (pinfunction "OFF_5") (pintype "input"))
      (node (ref "U1") (pin "8") (pinfunction "STBY_8") (pintype "input"))
    )
    (net (code "51") (name "TEMP") (class "Default")
      (node (ref "IC1") (pin "14") (pinfunction "PD6(ADC3/ACMPN2/INT0/PCINT22)_14") (pintype "bidirectional"))
      (node (ref "R5") (pin "1") (pinfunction "1_1") (pintype "passive"))
      (node (ref "R6") (pin "1") (pinfunction "1_1") (pintype "passive"))
    )
    (net (code "52") (name "VCC") (class "Default")
      (node (ref "C1") (pin "1") (pinfunction "1_1") (pintype "passive"))
      (node (ref "C10") (pin "1") (pinfunction "1_1") (pintype "passive"))
      (node (ref "C13") (pin "1") (pinfunction "1_1") (pintype "passive"))
      (node (ref "C14") (pin "1") (pinfunction "1_1") (pintype "passive"))
      (node (ref "C17") (pin "1") (pinfunction "1_1") (pintype "passive"))
      (node (ref "C2") (pin "1") (pinfunction "1_1") (pintype "passive"))
      (node (ref "C6") (pin "1") (pinfunction "1_1") (pintype "passive"))
      (node (ref "C7") (pin "1") (pinfunction "1_1") (pintype "passive"))
      (node (ref "C8") (pin "A") (pinfunction "+_A") (pintype "passive"))
      (node (ref "D1") (pin "A") (pinfunction "A_A") (pintype "passive"))
      (node (ref "D2") (pin "A") (pinfunction "A_A") (pintype "passive"))
      (node (ref "D7") (pin "C") (pinfunction "C_C") (pintype "passive"))
      (node (ref "IC1") (pin "19") (pinfunction "AVCC_19") (pintype "power_in"))
      (node (ref "IC1") (pin "21") (pinfunction "AREF(ISRC)_21") (pintype "power_in"))
      (node (ref "IC1") (pin "4") (pinfunction "VCC_4") (pintype "power_in"))
      (node (ref "J3") (pin "5") (pinfunction "5_5") (pintype "passive"))
      (node (ref "R1") (pin "2") (pinfunction "2_2") (pintype "passive"))
      (node (ref "R5") (pin "2") (pinfunction "2_2") (pintype "passive"))
      (node (ref "R8") (pin "1") (pinfunction "1_1") (pintype "passive"))
      (node (ref "SJ1") (pin "2") (pinfunction "2_2") (pintype "passive"))
      (node (ref "U$1") (pin "1") (pinfunction "1_1") (pintype "passive"))
      (node (ref "U1") (pin "3") (pinfunction "VDD_3") (pintype "power_in"))
      (node (ref "U1") (pin "5") (pinfunction "VIO_5") (pintype "power_in"))
      (node (ref "U2") (pin "8") (pinfunction "VCC_8") (pintype "power_in"))
      (node (ref "U3") (pin "13") (pinfunction "CNT_EN_13") (pintype "bidirectional"))
      (node (ref "U3") (pin "14") (pinfunction "VDD_14") (pintype "bidirectional"))
      (node (ref "X1") (pin "2") (pinfunction "2_2") (pintype "passive"))
      (node (ref "X3") (pin "P3") (pinfunction "3_P3") (pintype "bidirectional"))
    )
    (net (code "53") (name "VDD") (class "Default")
      (node (ref "C9") (pin "+") (pinfunction "+_+") (pintype "passive"))
      (node (ref "F1") (pin "1") (pinfunction "1_1") (pintype "passive"))
      (node (ref "IC2") (pin "1") (pinfunction "VIN_1") (pintype "power_in"))
      (node (ref "U2") (pin "1") (pinfunction "IP+_1") (pintype "input"))
      (node (ref "U2") (pin "2") (pinfunction "IP+_2_2") (pintype "input"))
    )
    (net (code "54") (name "VDD_HS") (class "Default")
      (node (ref "C18") (pin "+") (pinfunction "+_+") (pintype "passive"))
      (node (ref "C22") (pin "+") (pinfunction "+_+") (pintype "passive"))
      (node (ref "C26") (pin "+") (pinfunction "+_+") (pintype "passive"))
      (node (ref "Q3") (pin "4") (pinfunction "D_4") (pintype "passive"))
      (node (ref "Q5") (pin "4") (pinfunction "D_4") (pintype "passive"))
      (node (ref "Q7") (pin "4") (pinfunction "D_4") (pintype "passive"))
      (node (ref "U2") (pin "3") (pinfunction "IP-_3") (pintype "input"))
      (node (ref "U2") (pin "4") (pinfunction "IP-_2_4") (pintype "input"))
    )
    (net (code "55") (name "WINDING_1") (class "Default")
      (node (ref "L2") (pin "2") (pinfunction "2_2") (pintype "passive"))
      (node (ref "X3") (pin "P7") (pinfunction "7_P7") (pintype "bidirectional"))
    )
    (net (code "56") (name "WINDING_2") (class "Default")
      (node (ref "L3") (pin "2") (pinfunction "2_2") (pintype "passive"))
      (node (ref "X3") (pin "P8") (pinfunction "8_P8") (pintype "bidirectional"))
    )
    (net (code "57") (name "WINDING_3") (class "Default")
      (node (ref "L4") (pin "2") (pinfunction "2_2") (pintype "passive"))
      (node (ref "X3") (pin "P4") (pinfunction "4_P4") (pintype "bidirectional"))
    )
    (net (code "58") (name "unconnected-(IC1-PB4(AMP0+{slash}PCINT4)-Pad24)") (class "Default")
      (node (ref "IC1") (pin "24") (pinfunction "PB4(AMP0+/PCINT4)_24") (pintype "bidirectional"))
    )
    (net (code "59") (name "unconnected-(IC1-PB5(ADC6{slash}INT2{slash}ACMPN1{slash}AMP2-{slash}PCINT5)-Pad26)") (class "Default")
      (node (ref "IC1") (pin "26") (pinfunction "PB5(ADC6/INT2/ACMPN1/AMP2-/PCINT5)_26") (pintype "bidirectional"))
    )
    (net (code "60") (name "unconnected-(U3-DFLAG{slash}-Pad9)") (class "Default")
      (node (ref "U3") (pin "9") (pinfunction "DFLAG/_9") (pintype "bidirectional"))
    )
    (net (code "61") (name "unconnected-(U4-NC-Pad5)") (class "Default")
      (node (ref "U4") (pin "5") (pinfunction "NC_5") (pintype "no_connect"))
    )
    (net (code "62") (name "unconnected-(U5-NC-Pad5)") (class "Default")
      (node (ref "U5") (pin "5") (pinfunction "NC_5") (pintype "no_connect"))
    )
    (net (code "63") (name "unconnected-(U6-NC-Pad5)") (class "Default")
      (node (ref "U6") (pin "5") (pinfunction "NC_5") (pintype "no_connect"))
    )
  )
)
